# ESP-RGB.net
KiCad netlist of a schematic drawn in EAGLE
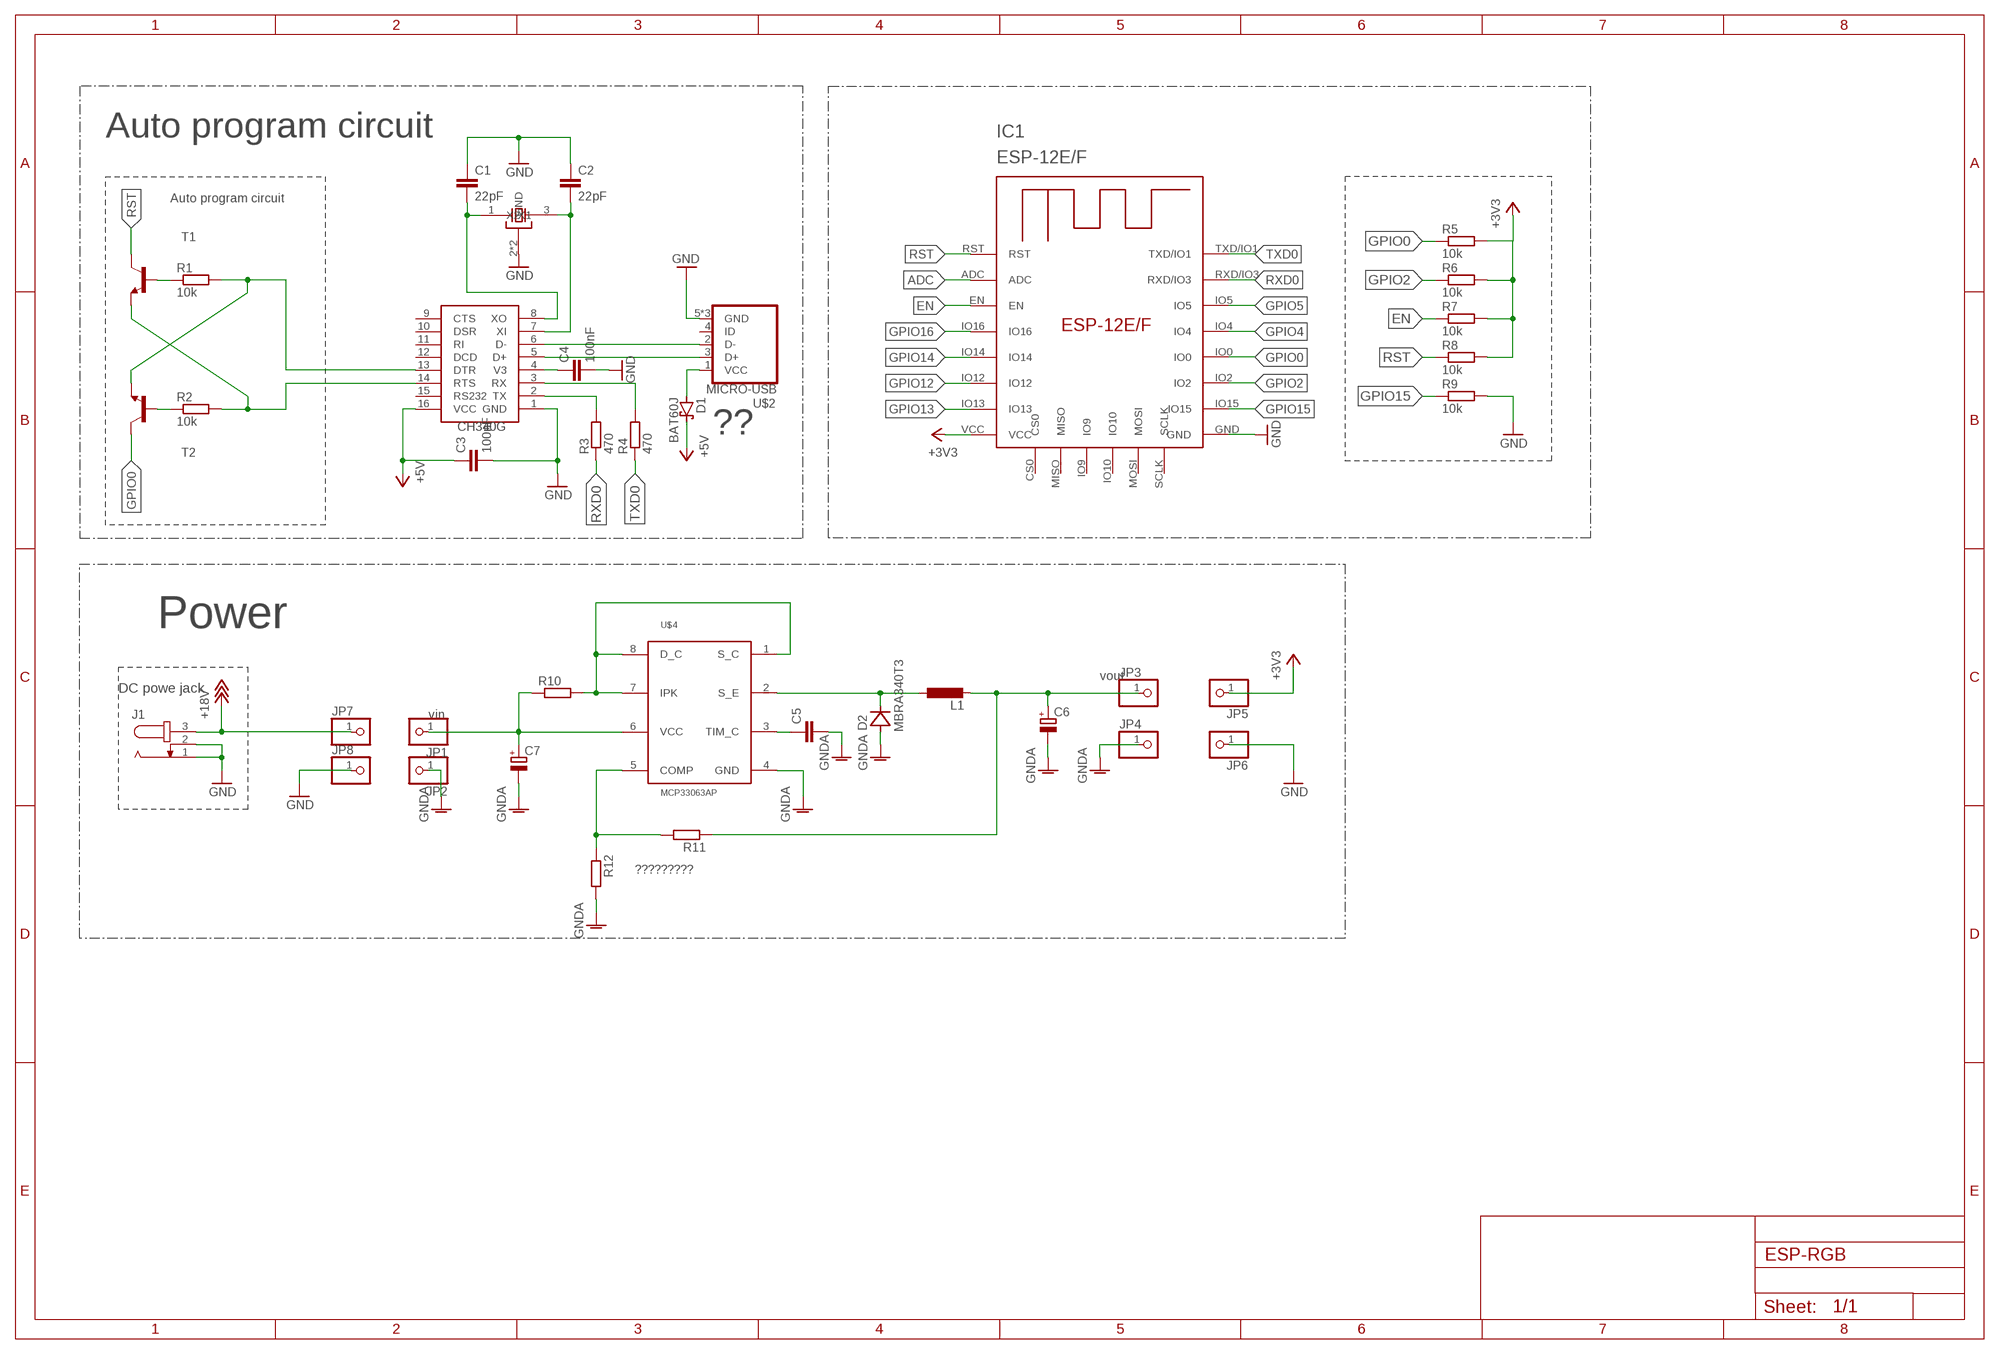
[diagram p0: schematic, sheet 1]

(export (version "E")
  (design (tool "Eeschema 10.0.6"))
  (components
    (comp (ref "C1")
      (value "22pF")
      (footprint "eagle-import:C0805K")
      (libsource (lib "eagle-import") (part "C-EUC0805K"))
    )
    (comp (ref "C2")
      (value "22pF")
      (footprint "eagle-import:C0805K")
      (libsource (lib "eagle-import") (part "C-EUC0805K"))
    )
    (comp (ref "C3")
      (value "100nF")
      (footprint "eagle-import:C0805K")
      (libsource (lib "eagle-import") (part "C-EUC0805K"))
    )
    (comp (ref "C4")
      (value "100nF")
      (footprint "eagle-import:C0805K")
      (libsource (lib "eagle-import") (part "C-EUC0805K"))
    )
    (comp (ref "C5")
      (value "C-EUC0805K")
      (footprint "eagle-import:C0805K")
      (libsource (lib "eagle-import") (part "C-EUC0805K"))
    )
    (comp (ref "C6")
      (value "CPOL-EU153CLV-0505")
      (footprint "eagle-import:153CLV-0505")
      (libsource (lib "eagle-import") (part "CPOL-EU153CLV-0505"))
    )
    (comp (ref "C7")
      (value "CPOL-EU153CLV-0505")
      (footprint "eagle-import:153CLV-0505")
      (libsource (lib "eagle-import") (part "CPOL-EU153CLV-0505"))
    )
    (comp (ref "D1")
      (value "BAT60J")
      (footprint "eagle-import:SOD323_ST")
      (libsource (lib "eagle-import") (part "BAT60J"))
    )
    (comp (ref "D2")
      (value "MBRA340T3")
      (footprint "eagle-import:SMA")
      (libsource (lib "eagle-import") (part "MBRA340T3"))
    )
    (comp (ref "IC1")
      (value "ESP-12E/F")
      (footprint "eagle-import:ESP-12E")
      (libsource (lib "eagle-import") (part "ESP-12E/F"))
    )
    (comp (ref "J1")
      (value "JACK-PLUG0")
      (footprint "eagle-import:SPC4077")
      (libsource (lib "eagle-import") (part "JACK-PLUG0"))
    )
    (comp (ref "JP1")
      (value "PINHD-1X1")
      (footprint "eagle-import:1X01")
      (libsource (lib "eagle-import") (part "PINHD-1X1"))
    )
    (comp (ref "JP2")
      (value "PINHD-1X1")
      (footprint "eagle-import:1X01")
      (libsource (lib "eagle-import") (part "PINHD-1X1"))
    )
    (comp (ref "JP3")
      (value "PINHD-1X1")
      (footprint "eagle-import:1X01")
      (libsource (lib "eagle-import") (part "PINHD-1X1"))
    )
    (comp (ref "JP4")
      (value "PINHD-1X1")
      (footprint "eagle-import:1X01")
      (libsource (lib "eagle-import") (part "PINHD-1X1"))
    )
    (comp (ref "JP5")
      (value "PINHD-1X1")
      (footprint "eagle-import:1X01")
      (libsource (lib "eagle-import") (part "PINHD-1X1"))
    )
    (comp (ref "JP6")
      (value "PINHD-1X1")
      (footprint "eagle-import:1X01")
      (libsource (lib "eagle-import") (part "PINHD-1X1"))
    )
    (comp (ref "JP7")
      (value "PINHD-1X1")
      (footprint "eagle-import:1X01")
      (libsource (lib "eagle-import") (part "PINHD-1X1"))
    )
    (comp (ref "JP8")
      (value "PINHD-1X1")
      (footprint "eagle-import:1X01")
      (libsource (lib "eagle-import") (part "PINHD-1X1"))
    )
    (comp (ref "L1")
      (value "L-EUPIS2816")
      (footprint "eagle-import:PIS2816")
      (libsource (lib "eagle-import") (part "L-EUPIS2816"))
    )
    (comp (ref "R1")
      (value "10k")
      (footprint "eagle-import:R0603")
      (libsource (lib "eagle-import") (part "R-EU_R0603"))
    )
    (comp (ref "R2")
      (value "10k")
      (footprint "eagle-import:R0603")
      (libsource (lib "eagle-import") (part "R-EU_R0603"))
    )
    (comp (ref "R3")
      (value "470")
      (footprint "eagle-import:R0603")
      (libsource (lib "eagle-import") (part "R-EU_R0603"))
    )
    (comp (ref "R4")
      (value "470")
      (footprint "eagle-import:R0603")
      (libsource (lib "eagle-import") (part "R-EU_R0603"))
    )
    (comp (ref "R5")
      (value "10k")
      (footprint "eagle-import:R0603")
      (libsource (lib "eagle-import") (part "R-EU_R0603"))
    )
    (comp (ref "R6")
      (value "10k")
      (footprint "eagle-import:R0603")
      (libsource (lib "eagle-import") (part "R-EU_R0603"))
    )
    (comp (ref "R7")
      (value "10k")
      (footprint "eagle-import:R0603")
      (libsource (lib "eagle-import") (part "R-EU_R0603"))
    )
    (comp (ref "R8")
      (value "10k")
      (footprint "eagle-import:R0603")
      (libsource (lib "eagle-import") (part "R-EU_R0603"))
    )
    (comp (ref "R9")
      (value "10k")
      (footprint "eagle-import:R0603")
      (libsource (lib "eagle-import") (part "R-EU_R0603"))
    )
    (comp (ref "R10")
      (value "R-EU_R1206W")
      (footprint "eagle-import:R1206W")
      (libsource (lib "eagle-import") (part "R-EU_R1206W"))
    )
    (comp (ref "R11")
      (value "R-EU_R0603")
      (footprint "eagle-import:R0603")
      (libsource (lib "eagle-import") (part "R-EU_R0603"))
    )
    (comp (ref "R12")
      (value "R-EU_R0603")
      (footprint "eagle-import:R0603")
      (libsource (lib "eagle-import") (part "R-EU_R0603"))
    )
    (comp (ref "T1")
      (value "BC817-16-NPN-SOT23-BEC")
      (footprint "eagle-import:SOT23-BEC")
      (libsource (lib "eagle-import") (part "-NPN-SOT23-BECBC817-16"))
    )
    (comp (ref "T2")
      (value "BC817-16-NPN-SOT23-BEC")
      (footprint "eagle-import:SOT23-BEC")
      (libsource (lib "eagle-import") (part "-NPN-SOT23-BECBC817-16"))
    )
    (comp (ref "U$1")
      (value "CH340G")
      (footprint "eagle-import:SOIC16")
      (libsource (lib "eagle-import") (part "CH340G"))
    )
    (comp (ref "U$2")
      (value "MICRO-USB")
      (footprint "eagle-import:MICRO-USB")
      (libsource (lib "eagle-import") (part "MICRO-USB"))
    )
    (comp (ref "U$3")
      (value "CTS_32X25_SMD")
      (footprint "eagle-import:CTS_32X25")
      (libsource (lib "eagle-import") (part "CTS_32X25_SMD"))
    )
    (comp (ref "U$4")
      (value "MCP33063AP")
      (footprint "eagle-import:DIL08")
      (libsource (lib "eagle-import") (part "MCP33063AP"))
    )
  )
  (nets
    (net (code "1") (name "+3V3") (class "Default")
      (node (ref "IC1") (pin "VCC") (pinfunction "VCC_VCC") (pintype "power_in"))
      (node (ref "JP5") (pin "1") (pinfunction "1_1") (pintype "passive"))
      (node (ref "R5") (pin "2") (pinfunction "2_2") (pintype "passive"))
      (node (ref "R6") (pin "2") (pinfunction "2_2") (pintype "passive"))
      (node (ref "R7") (pin "2") (pinfunction "2_2") (pintype "passive"))
      (node (ref "R8") (pin "2") (pinfunction "2_2") (pintype "passive"))
    )
    (net (code "2") (name "+5V") (class "Default")
      (node (ref "C3") (pin "1") (pinfunction "1_1") (pintype "passive"))
      (node (ref "D1") (pin "C") (pinfunction "C_C") (pintype "passive"))
      (node (ref "U$1") (pin "16") (pinfunction "VCC_16") (pintype "bidirectional"))
    )
    (net (code "3") (name "+18V") (class "Default")
      (node (ref "J1") (pin "3") (pinfunction "3_3") (pintype "passive"))
      (node (ref "JP7") (pin "1") (pinfunction "1_1") (pintype "passive"))
    )
    (net (code "4") (name "ADC") (class "Default")
      (node (ref "IC1") (pin "ADC") (pinfunction "ADC_ADC") (pintype "bidirectional"))
    )
    (net (code "5") (name "EN") (class "Default")
      (node (ref "IC1") (pin "EN") (pinfunction "EN_EN") (pintype "bidirectional"))
      (node (ref "R7") (pin "1") (pinfunction "1_1") (pintype "passive"))
    )
    (net (code "6") (name "GND") (class "Default")
      (node (ref "C1") (pin "1") (pinfunction "1_1") (pintype "passive"))
      (node (ref "C2") (pin "1") (pinfunction "1_1") (pintype "passive"))
      (node (ref "C3") (pin "2") (pinfunction "2_2") (pintype "passive"))
      (node (ref "C4") (pin "2") (pinfunction "2_2") (pintype "passive"))
      (node (ref "IC1") (pin "GND") (pinfunction "GND_GND") (pintype "power_in"))
      (node (ref "J1") (pin "1") (pinfunction "1_1") (pintype "passive"))
      (node (ref "J1") (pin "2") (pinfunction "2_2") (pintype "passive"))
      (node (ref "JP6") (pin "1") (pinfunction "1_1") (pintype "passive"))
      (node (ref "JP8") (pin "1") (pinfunction "1_1") (pintype "passive"))
      (node (ref "R9") (pin "2") (pinfunction "2_2") (pintype "passive"))
      (node (ref "U$1") (pin "1") (pinfunction "GND_1") (pintype "bidirectional"))
      (node (ref "U$2") (pin "5") (pinfunction "GND_5") (pintype "power_in"))
      (node (ref "U$2") (pin "GND1") (pinfunction "GND_GND1") (pintype "power_in"))
      (node (ref "U$2") (pin "GND2") (pinfunction "GND_GND2") (pintype "power_in"))
      (node (ref "U$3") (pin "2") (pinfunction "GND_2") (pintype "power_in"))
      (node (ref "U$3") (pin "4") (pinfunction "GND_4") (pintype "power_in"))
    )
    (net (code "7") (name "GNDA") (class "Default")
      (node (ref "C5") (pin "2") (pinfunction "2_2") (pintype "passive"))
      (node (ref "C6") (pin "-") (pinfunction "-_-") (pintype "passive"))
      (node (ref "C7") (pin "-") (pinfunction "-_-") (pintype "passive"))
      (node (ref "D2") (pin "A") (pinfunction "A_A") (pintype "passive"))
      (node (ref "JP2") (pin "1") (pinfunction "1_1") (pintype "passive"))
      (node (ref "JP4") (pin "1") (pinfunction "1_1") (pintype "passive"))
      (node (ref "R12") (pin "2") (pinfunction "2_2") (pintype "passive"))
      (node (ref "U$4") (pin "4") (pinfunction "GND_4") (pintype "bidirectional"))
    )
    (net (code "8") (name "GPIO0") (class "Default")
      (node (ref "IC1") (pin "IO0") (pinfunction "IO0_IO0") (pintype "bidirectional"))
      (node (ref "R5") (pin "1") (pinfunction "1_1") (pintype "passive"))
      (node (ref "T2") (pin "C") (pinfunction "C_C") (pintype "passive"))
    )
    (net (code "9") (name "GPIO2") (class "Default")
      (node (ref "IC1") (pin "IO2") (pinfunction "IO2_IO2") (pintype "bidirectional"))
      (node (ref "R6") (pin "1") (pinfunction "1_1") (pintype "passive"))
    )
    (net (code "10") (name "GPIO4") (class "Default")
      (node (ref "IC1") (pin "IO4") (pinfunction "IO4_IO4") (pintype "bidirectional"))
    )
    (net (code "11") (name "GPIO5") (class "Default")
      (node (ref "IC1") (pin "IO5") (pinfunction "IO5_IO5") (pintype "bidirectional"))
    )
    (net (code "12") (name "GPIO12") (class "Default")
      (node (ref "IC1") (pin "IO12") (pinfunction "IO12_IO12") (pintype "bidirectional"))
    )
    (net (code "13") (name "GPIO13") (class "Default")
      (node (ref "IC1") (pin "IO13") (pinfunction "IO13_IO13") (pintype "bidirectional"))
    )
    (net (code "14") (name "GPIO14") (class "Default")
      (node (ref "IC1") (pin "IO14") (pinfunction "IO14_IO14") (pintype "bidirectional"))
    )
    (net (code "15") (name "GPIO15") (class "Default")
      (node (ref "IC1") (pin "IO15") (pinfunction "IO15_IO15") (pintype "bidirectional"))
      (node (ref "R9") (pin "1") (pinfunction "1_1") (pintype "passive"))
    )
    (net (code "16") (name "GPIO16") (class "Default")
      (node (ref "IC1") (pin "IO16") (pinfunction "IO16_IO16") (pintype "bidirectional"))
    )
    (net (code "17") (name "Net-(C6-Pad+)") (class "Default")
      (node (ref "C6") (pin "+") (pinfunction "+_+") (pintype "passive"))
      (node (ref "JP3") (pin "1") (pinfunction "1_1") (pintype "passive"))
      (node (ref "L1") (pin "2") (pinfunction "2_2") (pintype "passive"))
      (node (ref "R11") (pin "1") (pinfunction "1_1") (pintype "passive"))
    )
    (net (code "18") (name "Net-(R1-Pad1)") (class "Default")
      (node (ref "R1") (pin "1") (pinfunction "1_1") (pintype "passive"))
      (node (ref "T1") (pin "B") (pinfunction "B_B") (pintype "passive"))
    )
    (net (code "19") (name "Net-(R2-Pad1)") (class "Default")
      (node (ref "R2") (pin "1") (pinfunction "1_1") (pintype "passive"))
      (node (ref "T2") (pin "B") (pinfunction "B_B") (pintype "passive"))
    )
    (net (code "20") (name "Net-(U$1-D+)") (class "Default")
      (node (ref "U$1") (pin "5") (pinfunction "D+_5") (pintype "bidirectional"))
      (node (ref "U$2") (pin "3") (pinfunction "D+_3") (pintype "bidirectional"))
    )
    (net (code "21") (name "Net-(U$1-D-)") (class "Default")
      (node (ref "U$1") (pin "6") (pinfunction "D-_6") (pintype "bidirectional"))
      (node (ref "U$2") (pin "2") (pinfunction "D-_2") (pintype "bidirectional"))
    )
    (net (code "22") (name "Net-(U$1-DTR)") (class "Default")
      (node (ref "R1") (pin "2") (pinfunction "2_2") (pintype "passive"))
      (node (ref "T2") (pin "E") (pinfunction "E_E") (pintype "passive"))
      (node (ref "U$1") (pin "13") (pinfunction "DTR_13") (pintype "bidirectional"))
    )
    (net (code "23") (name "Net-(U$1-RTS)") (class "Default")
      (node (ref "R2") (pin "2") (pinfunction "2_2") (pintype "passive"))
      (node (ref "T1") (pin "E") (pinfunction "E_E") (pintype "passive"))
      (node (ref "U$1") (pin "14") (pinfunction "RTS_14") (pintype "bidirectional"))
    )
    (net (code "24") (name "Net-(U$1-RX)") (class "Default")
      (node (ref "R4") (pin "2") (pinfunction "2_2") (pintype "passive"))
      (node (ref "U$1") (pin "3") (pinfunction "RX_3") (pintype "bidirectional"))
    )
    (net (code "25") (name "Net-(U$1-TX)") (class "Default")
      (node (ref "R3") (pin "2") (pinfunction "2_2") (pintype "passive"))
      (node (ref "U$1") (pin "2") (pinfunction "TX_2") (pintype "bidirectional"))
    )
    (net (code "26") (name "Net-(U$1-V3)") (class "Default")
      (node (ref "C4") (pin "1") (pinfunction "1_1") (pintype "passive"))
      (node (ref "U$1") (pin "4") (pinfunction "V3_4") (pintype "bidirectional"))
    )
    (net (code "27") (name "Net-(U$1-XI)") (class "Default")
      (node (ref "C2") (pin "2") (pinfunction "2_2") (pintype "passive"))
      (node (ref "U$1") (pin "7") (pinfunction "XI_7") (pintype "bidirectional"))
      (node (ref "U$3") (pin "3") (pinfunction "X2_3") (pintype "bidirectional"))
    )
    (net (code "28") (name "Net-(U$1-XO)") (class "Default")
      (node (ref "C1") (pin "2") (pinfunction "2_2") (pintype "passive"))
      (node (ref "U$1") (pin "8") (pinfunction "XO_8") (pintype "bidirectional"))
      (node (ref "U$3") (pin "1") (pinfunction "X1_1") (pintype "bidirectional"))
    )
    (net (code "29") (name "Net-(U$2-VCC)") (class "Default")
      (node (ref "D1") (pin "A") (pinfunction "A_A") (pintype "passive"))
      (node (ref "U$2") (pin "1") (pinfunction "VCC_1") (pintype "power_in"))
    )
    (net (code "30") (name "Net-(U$4-COMP)") (class "Default")
      (node (ref "R11") (pin "2") (pinfunction "2_2") (pintype "passive"))
      (node (ref "R12") (pin "1") (pinfunction "1_1") (pintype "passive"))
      (node (ref "U$4") (pin "5") (pinfunction "COMP_5") (pintype "bidirectional"))
    )
    (net (code "31") (name "Net-(U$4-D_C)") (class "Default")
      (node (ref "R10") (pin "2") (pinfunction "2_2") (pintype "passive"))
      (node (ref "U$4") (pin "1") (pinfunction "S_C_1") (pintype "bidirectional"))
      (node (ref "U$4") (pin "7") (pinfunction "IPK_7") (pintype "bidirectional"))
      (node (ref "U$4") (pin "8") (pinfunction "D_C_8") (pintype "bidirectional"))
    )
    (net (code "32") (name "Net-(U$4-S_E)") (class "Default")
      (node (ref "D2") (pin "C") (pinfunction "C_C") (pintype "passive"))
      (node (ref "L1") (pin "1") (pinfunction "1_1") (pintype "passive"))
      (node (ref "U$4") (pin "2") (pinfunction "S_E_2") (pintype "bidirectional"))
    )
    (net (code "33") (name "Net-(U$4-TIM_C)") (class "Default")
      (node (ref "C5") (pin "1") (pinfunction "1_1") (pintype "passive"))
      (node (ref "U$4") (pin "3") (pinfunction "TIM_C_3") (pintype "bidirectional"))
    )
    (net (code "34") (name "Net-(U$4-VCC)") (class "Default")
      (node (ref "C7") (pin "+") (pinfunction "+_+") (pintype "passive"))
      (node (ref "JP1") (pin "1") (pinfunction "1_1") (pintype "passive"))
      (node (ref "R10") (pin "1") (pinfunction "1_1") (pintype "passive"))
      (node (ref "U$4") (pin "6") (pinfunction "VCC_6") (pintype "bidirectional"))
    )
    (net (code "35") (name "RST") (class "Default")
      (node (ref "IC1") (pin "RST") (pinfunction "RST_RST") (pintype "input"))
      (node (ref "R8") (pin "1") (pinfunction "1_1") (pintype "passive"))
      (node (ref "T1") (pin "C") (pinfunction "C_C") (pintype "passive"))
    )
    (net (code "36") (name "RXD0") (class "Default")
      (node (ref "IC1") (pin "RXD/IO3") (pinfunction "RXD/IO3_RXD/IO3") (pintype "bidirectional"))
      (node (ref "R3") (pin "1") (pinfunction "1_1") (pintype "passive"))
    )
    (net (code "37") (name "TXD0") (class "Default")
      (node (ref "IC1") (pin "TXD/IO1") (pinfunction "TXD/IO1_TXD/IO1") (pintype "bidirectional"))
      (node (ref "R4") (pin "1") (pinfunction "1_1") (pintype "passive"))
    )
    (net (code "38") (name "unconnected-(IC1-PadCS0)") (class "Default")
      (node (ref "IC1") (pin "CS0") (pinfunction "CS0_CS0") (pintype "bidirectional"))
    )
    (net (code "39") (name "unconnected-(IC1-PadIO9)") (class "Default")
      (node (ref "IC1") (pin "IO9") (pinfunction "IO9_IO9") (pintype "bidirectional"))
    )
    (net (code "40") (name "unconnected-(IC1-PadIO10)") (class "Default")
      (node (ref "IC1") (pin "IO10") (pinfunction "IO10_IO10") (pintype "bidirectional"))
    )
    (net (code "41") (name "unconnected-(IC1-PadMISO)") (class "Default")
      (node (ref "IC1") (pin "MISO") (pinfunction "MISO_MISO") (pintype "bidirectional"))
    )
    (net (code "42") (name "unconnected-(IC1-PadMOSI)") (class "Default")
      (node (ref "IC1") (pin "MOSI") (pinfunction "MOSI_MOSI") (pintype "bidirectional"))
    )
    (net (code "43") (name "unconnected-(IC1-PadSCLK)") (class "Default")
      (node (ref "IC1") (pin "SCLK") (pinfunction "SCLK_SCLK") (pintype "bidirectional"))
    )
    (net (code "44") (name "unconnected-(U$1-CTS-Pad9)") (class "Default")
      (node (ref "U$1") (pin "9") (pinfunction "CTS_9") (pintype "bidirectional"))
    )
    (net (code "45") (name "unconnected-(U$1-DCD-Pad12)") (class "Default")
      (node (ref "U$1") (pin "12") (pinfunction "DCD_12") (pintype "bidirectional"))
    )
    (net (code "46") (name "unconnected-(U$1-DSR-Pad10)") (class "Default")
      (node (ref "U$1") (pin "10") (pinfunction "DSR_10") (pintype "bidirectional"))
    )
    (net (code "47") (name "unconnected-(U$1-RI-Pad11)") (class "Default")
      (node (ref "U$1") (pin "11") (pinfunction "RI_11") (pintype "bidirectional"))
    )
    (net (code "48") (name "unconnected-(U$1-RS232-Pad15)") (class "Default")
      (node (ref "U$1") (pin "15") (pinfunction "RS232_15") (pintype "bidirectional"))
    )
    (net (code "49") (name "unconnected-(U$2-ID-Pad4)") (class "Default")
      (node (ref "U$2") (pin "4") (pinfunction "ID_4") (pintype "bidirectional"))
    )
  )
)
